# FRU_Programmer_LPC.net
KiCad netlist of a schematic drawn in Altium Designer
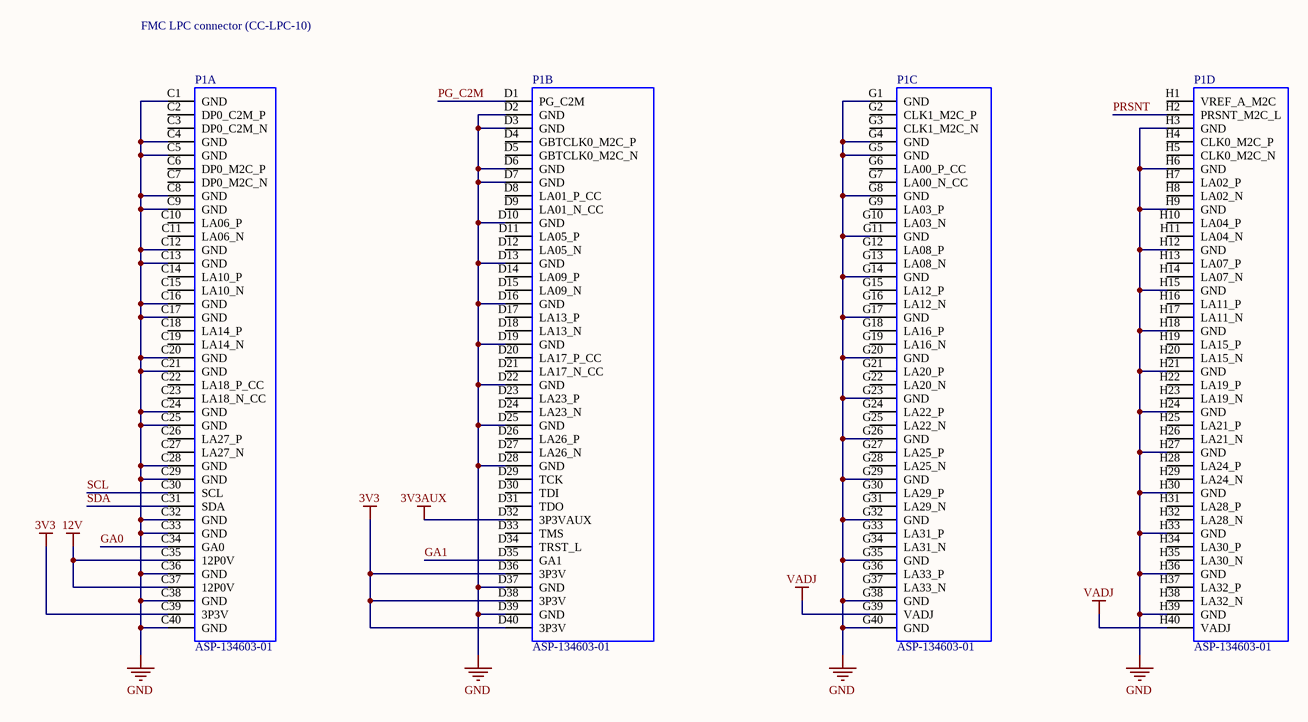
[diagram p0: FRU_Programmer_LPC.SchDoc]

(export (version "E")
  (design (tool "Eeschema 10.0.6"))
  (components
    (comp (ref "P1")
      (value "ASP-134603-01")
      (footprint "ASP-134603-01")
      (description "CC-LPC-10, FMC Low-pin count connector, lead free, 160 I/Os, female, 10 mm mated stack height")
      (fields (field (name "MANUFACTURER") "Samtec") (field (name "VITA PARTNUMBER") "CC-LPC-10"))
      (libsource (lib "VITA_57_FMC") (part "CC-LPC-10"))
    )
  )
  (nets
    (net (code "1") (name "/GA0") (class "Default")
      (node (ref "P1") (pin "C34") (pinfunction "GA0_C34") (pintype "passive"))
    )
    (net (code "2") (name "/GA1") (class "Default")
      (node (ref "P1") (pin "D35") (pinfunction "GA1_D35") (pintype "passive"))
    )
    (net (code "3") (name "/PG_C2M") (class "Default")
      (node (ref "P1") (pin "D1") (pinfunction "PG_C2M_D1") (pintype "passive"))
    )
    (net (code "4") (name "/PRSNT") (class "Default")
      (node (ref "P1") (pin "H2") (pinfunction "PRSNT_M2C_L_H2") (pintype "passive"))
    )
    (net (code "5") (name "/SCL") (class "Default")
      (node (ref "P1") (pin "C30") (pinfunction "SCL_C30") (pintype "passive"))
    )
    (net (code "6") (name "/SDA") (class "Default")
      (node (ref "P1") (pin "C31") (pinfunction "SDA_C31") (pintype "passive"))
    )
    (net (code "7") (name "3V3") (class "Default")
      (node (ref "P1") (pin "C39") (pinfunction "3P3V_C39") (pintype "passive"))
      (node (ref "P1") (pin "D36") (pinfunction "3P3V_D36") (pintype "passive"))
      (node (ref "P1") (pin "D38") (pinfunction "3P3V_D38") (pintype "passive"))
      (node (ref "P1") (pin "D40") (pinfunction "3P3V_D40") (pintype "passive"))
    )
    (net (code "8") (name "3V3AUX") (class "Default")
      (node (ref "P1") (pin "D32") (pinfunction "3P3VAUX_D32") (pintype "passive"))
    )
    (net (code "9") (name "12V") (class "Default")
      (node (ref "P1") (pin "C35") (pinfunction "12P0V_C35") (pintype "passive"))
      (node (ref "P1") (pin "C37") (pinfunction "12P0V_C37") (pintype "passive"))
    )
    (net (code "10") (name "GND") (class "Default")
      (node (ref "P1") (pin "C1") (pinfunction "GND_C1") (pintype "passive"))
      (node (ref "P1") (pin "C12") (pinfunction "GND_C12") (pintype "passive"))
      (node (ref "P1") (pin "C13") (pinfunction "GND_C13") (pintype "passive"))
      (node (ref "P1") (pin "C16") (pinfunction "GND_C16") (pintype "passive"))
      (node (ref "P1") (pin "C17") (pinfunction "GND_C17") (pintype "passive"))
      (node (ref "P1") (pin "C20") (pinfunction "GND_C20") (pintype "passive"))
      (node (ref "P1") (pin "C21") (pinfunction "GND_C21") (pintype "passive"))
      (node (ref "P1") (pin "C24") (pinfunction "GND_C24") (pintype "passive"))
      (node (ref "P1") (pin "C25") (pinfunction "GND_C25") (pintype "passive"))
      (node (ref "P1") (pin "C28") (pinfunction "GND_C28") (pintype "passive"))
      (node (ref "P1") (pin "C29") (pinfunction "GND_C29") (pintype "passive"))
      (node (ref "P1") (pin "C32") (pinfunction "GND_C32") (pintype "passive"))
      (node (ref "P1") (pin "C33") (pinfunction "GND_C33") (pintype "passive"))
      (node (ref "P1") (pin "C36") (pinfunction "GND_C36") (pintype "passive"))
      (node (ref "P1") (pin "C38") (pinfunction "GND_C38") (pintype "passive"))
      (node (ref "P1") (pin "C4") (pinfunction "GND_C4") (pintype "passive"))
      (node (ref "P1") (pin "C40") (pinfunction "GND_C40") (pintype "passive"))
      (node (ref "P1") (pin "C5") (pinfunction "GND_C5") (pintype "passive"))
      (node (ref "P1") (pin "C8") (pinfunction "GND_C8") (pintype "passive"))
      (node (ref "P1") (pin "C9") (pinfunction "GND_C9") (pintype "passive"))
      (node (ref "P1") (pin "D10") (pinfunction "GND_D10") (pintype "passive"))
      (node (ref "P1") (pin "D13") (pinfunction "GND_D13") (pintype "passive"))
      (node (ref "P1") (pin "D16") (pinfunction "GND_D16") (pintype "passive"))
      (node (ref "P1") (pin "D19") (pinfunction "GND_D19") (pintype "passive"))
      (node (ref "P1") (pin "D2") (pinfunction "GND_D2") (pintype "passive"))
      (node (ref "P1") (pin "D22") (pinfunction "GND_D22") (pintype "passive"))
      (node (ref "P1") (pin "D25") (pinfunction "GND_D25") (pintype "passive"))
      (node (ref "P1") (pin "D28") (pinfunction "GND_D28") (pintype "passive"))
      (node (ref "P1") (pin "D3") (pinfunction "GND_D3") (pintype "passive"))
      (node (ref "P1") (pin "D37") (pinfunction "GND_D37") (pintype "passive"))
      (node (ref "P1") (pin "D39") (pinfunction "GND_D39") (pintype "passive"))
      (node (ref "P1") (pin "D6") (pinfunction "GND_D6") (pintype "passive"))
      (node (ref "P1") (pin "D7") (pinfunction "GND_D7") (pintype "passive"))
      (node (ref "P1") (pin "G1") (pinfunction "GND_G1") (pintype "passive"))
      (node (ref "P1") (pin "G11") (pinfunction "GND_G11") (pintype "passive"))
      (node (ref "P1") (pin "G14") (pinfunction "GND_G14") (pintype "passive"))
      (node (ref "P1") (pin "G17") (pinfunction "GND_G17") (pintype "passive"))
      (node (ref "P1") (pin "G20") (pinfunction "GND_G20") (pintype "passive"))
      (node (ref "P1") (pin "G23") (pinfunction "GND_G23") (pintype "passive"))
      (node (ref "P1") (pin "G26") (pinfunction "GND_G26") (pintype "passive"))
      (node (ref "P1") (pin "G29") (pinfunction "GND_G29") (pintype "passive"))
      (node (ref "P1") (pin "G32") (pinfunction "GND_G32") (pintype "passive"))
      (node (ref "P1") (pin "G35") (pinfunction "GND_G35") (pintype "passive"))
      (node (ref "P1") (pin "G38") (pinfunction "GND_G38") (pintype "passive"))
      (node (ref "P1") (pin "G4") (pinfunction "GND_G4") (pintype "passive"))
      (node (ref "P1") (pin "G40") (pinfunction "GND_G40") (pintype "passive"))
      (node (ref "P1") (pin "G5") (pinfunction "GND_G5") (pintype "passive"))
      (node (ref "P1") (pin "G8") (pinfunction "GND_G8") (pintype "passive"))
      (node (ref "P1") (pin "H12") (pinfunction "GND_H12") (pintype "passive"))
      (node (ref "P1") (pin "H15") (pinfunction "GND_H15") (pintype "passive"))
      (node (ref "P1") (pin "H18") (pinfunction "GND_H18") (pintype "passive"))
      (node (ref "P1") (pin "H21") (pinfunction "GND_H21") (pintype "passive"))
      (node (ref "P1") (pin "H24") (pinfunction "GND_H24") (pintype "passive"))
      (node (ref "P1") (pin "H27") (pinfunction "GND_H27") (pintype "passive"))
      (node (ref "P1") (pin "H3") (pinfunction "GND_H3") (pintype "passive"))
      (node (ref "P1") (pin "H30") (pinfunction "GND_H30") (pintype "passive"))
      (node (ref "P1") (pin "H33") (pinfunction "GND_H33") (pintype "passive"))
      (node (ref "P1") (pin "H36") (pinfunction "GND_H36") (pintype "passive"))
      (node (ref "P1") (pin "H39") (pinfunction "GND_H39") (pintype "passive"))
      (node (ref "P1") (pin "H6") (pinfunction "GND_H6") (pintype "passive"))
      (node (ref "P1") (pin "H9") (pinfunction "GND_H9") (pintype "passive"))
    )
    (net (code "11") (name "VADJ") (class "Default")
      (node (ref "P1") (pin "G39") (pinfunction "VADJ_G39") (pintype "passive"))
      (node (ref "P1") (pin "H40") (pinfunction "VADJ_H40") (pintype "passive"))
    )
    (net (code "12") (name "unconnected-(P1A-DP0_C2M_N-PadC3)") (class "Default")
      (node (ref "P1") (pin "C3") (pinfunction "DP0_C2M_N_C3") (pintype "passive"))
    )
    (net (code "13") (name "unconnected-(P1A-DP0_C2M_P-PadC2)") (class "Default")
      (node (ref "P1") (pin "C2") (pinfunction "DP0_C2M_P_C2") (pintype "passive"))
    )
    (net (code "14") (name "unconnected-(P1A-DP0_M2C_N-PadC7)") (class "Default")
      (node (ref "P1") (pin "C7") (pinfunction "DP0_M2C_N_C7") (pintype "passive"))
    )
    (net (code "15") (name "unconnected-(P1A-DP0_M2C_P-PadC6)") (class "Default")
      (node (ref "P1") (pin "C6") (pinfunction "DP0_M2C_P_C6") (pintype "passive"))
    )
    (net (code "16") (name "unconnected-(P1A-LA06_N-PadC11)") (class "Default")
      (node (ref "P1") (pin "C11") (pinfunction "LA06_N_C11") (pintype "passive"))
    )
    (net (code "17") (name "unconnected-(P1A-LA06_P-PadC10)") (class "Default")
      (node (ref "P1") (pin "C10") (pinfunction "LA06_P_C10") (pintype "passive"))
    )
    (net (code "18") (name "unconnected-(P1A-LA10_N-PadC15)") (class "Default")
      (node (ref "P1") (pin "C15") (pinfunction "LA10_N_C15") (pintype "passive"))
    )
    (net (code "19") (name "unconnected-(P1A-LA10_P-PadC14)") (class "Default")
      (node (ref "P1") (pin "C14") (pinfunction "LA10_P_C14") (pintype "passive"))
    )
    (net (code "20") (name "unconnected-(P1A-LA14_N-PadC19)") (class "Default")
      (node (ref "P1") (pin "C19") (pinfunction "LA14_N_C19") (pintype "passive"))
    )
    (net (code "21") (name "unconnected-(P1A-LA14_P-PadC18)") (class "Default")
      (node (ref "P1") (pin "C18") (pinfunction "LA14_P_C18") (pintype "passive"))
    )
    (net (code "22") (name "unconnected-(P1A-LA18_N_CC-PadC23)") (class "Default")
      (node (ref "P1") (pin "C23") (pinfunction "LA18_N_CC_C23") (pintype "passive"))
    )
    (net (code "23") (name "unconnected-(P1A-LA18_P_CC-PadC22)") (class "Default")
      (node (ref "P1") (pin "C22") (pinfunction "LA18_P_CC_C22") (pintype "passive"))
    )
    (net (code "24") (name "unconnected-(P1A-LA27_N-PadC27)") (class "Default")
      (node (ref "P1") (pin "C27") (pinfunction "LA27_N_C27") (pintype "passive"))
    )
    (net (code "25") (name "unconnected-(P1A-LA27_P-PadC26)") (class "Default")
      (node (ref "P1") (pin "C26") (pinfunction "LA27_P_C26") (pintype "passive"))
    )
    (net (code "26") (name "unconnected-(P1B-GBTCLK0_M2C_N-PadD5)") (class "Default")
      (node (ref "P1") (pin "D5") (pinfunction "GBTCLK0_M2C_N_D5") (pintype "passive"))
    )
    (net (code "27") (name "unconnected-(P1B-GBTCLK0_M2C_P-PadD4)") (class "Default")
      (node (ref "P1") (pin "D4") (pinfunction "GBTCLK0_M2C_P_D4") (pintype "passive"))
    )
    (net (code "28") (name "unconnected-(P1B-LA01_N_CC-PadD9)") (class "Default")
      (node (ref "P1") (pin "D9") (pinfunction "LA01_N_CC_D9") (pintype "passive"))
    )
    (net (code "29") (name "unconnected-(P1B-LA01_P_CC-PadD8)") (class "Default")
      (node (ref "P1") (pin "D8") (pinfunction "LA01_P_CC_D8") (pintype "passive"))
    )
    (net (code "30") (name "unconnected-(P1B-LA05_N-PadD12)") (class "Default")
      (node (ref "P1") (pin "D12") (pinfunction "LA05_N_D12") (pintype "passive"))
    )
    (net (code "31") (name "unconnected-(P1B-LA05_P-PadD11)") (class "Default")
      (node (ref "P1") (pin "D11") (pinfunction "LA05_P_D11") (pintype "passive"))
    )
    (net (code "32") (name "unconnected-(P1B-LA09_N-PadD15)") (class "Default")
      (node (ref "P1") (pin "D15") (pinfunction "LA09_N_D15") (pintype "passive"))
    )
    (net (code "33") (name "unconnected-(P1B-LA09_P-PadD14)") (class "Default")
      (node (ref "P1") (pin "D14") (pinfunction "LA09_P_D14") (pintype "passive"))
    )
    (net (code "34") (name "unconnected-(P1B-LA13_N-PadD18)") (class "Default")
      (node (ref "P1") (pin "D18") (pinfunction "LA13_N_D18") (pintype "passive"))
    )
    (net (code "35") (name "unconnected-(P1B-LA13_P-PadD17)") (class "Default")
      (node (ref "P1") (pin "D17") (pinfunction "LA13_P_D17") (pintype "passive"))
    )
    (net (code "36") (name "unconnected-(P1B-LA17_N_CC-PadD21)") (class "Default")
      (node (ref "P1") (pin "D21") (pinfunction "LA17_N_CC_D21") (pintype "passive"))
    )
    (net (code "37") (name "unconnected-(P1B-LA17_P_CC-PadD20)") (class "Default")
      (node (ref "P1") (pin "D20") (pinfunction "LA17_P_CC_D20") (pintype "passive"))
    )
    (net (code "38") (name "unconnected-(P1B-LA23_N-PadD24)") (class "Default")
      (node (ref "P1") (pin "D24") (pinfunction "LA23_N_D24") (pintype "passive"))
    )
    (net (code "39") (name "unconnected-(P1B-LA23_P-PadD23)") (class "Default")
      (node (ref "P1") (pin "D23") (pinfunction "LA23_P_D23") (pintype "passive"))
    )
    (net (code "40") (name "unconnected-(P1B-LA26_N-PadD27)") (class "Default")
      (node (ref "P1") (pin "D27") (pinfunction "LA26_N_D27") (pintype "passive"))
    )
    (net (code "41") (name "unconnected-(P1B-LA26_P-PadD26)") (class "Default")
      (node (ref "P1") (pin "D26") (pinfunction "LA26_P_D26") (pintype "passive"))
    )
    (net (code "42") (name "unconnected-(P1B-TCK-PadD29)") (class "Default")
      (node (ref "P1") (pin "D29") (pinfunction "TCK_D29") (pintype "passive"))
    )
    (net (code "43") (name "unconnected-(P1B-TDI-PadD30)") (class "Default")
      (node (ref "P1") (pin "D30") (pinfunction "TDI_D30") (pintype "passive"))
    )
    (net (code "44") (name "unconnected-(P1B-TDO-PadD31)") (class "Default")
      (node (ref "P1") (pin "D31") (pinfunction "TDO_D31") (pintype "passive"))
    )
    (net (code "45") (name "unconnected-(P1B-TMS-PadD33)") (class "Default")
      (node (ref "P1") (pin "D33") (pinfunction "TMS_D33") (pintype "passive"))
    )
    (net (code "46") (name "unconnected-(P1B-TRST_L-PadD34)") (class "Default")
      (node (ref "P1") (pin "D34") (pinfunction "TRST_L_D34") (pintype "passive"))
    )
    (net (code "47") (name "unconnected-(P1C-CLK1_M2C_N-PadG3)") (class "Default")
      (node (ref "P1") (pin "G3") (pinfunction "CLK1_M2C_N_G3") (pintype "passive"))
    )
    (net (code "48") (name "unconnected-(P1C-CLK1_M2C_P-PadG2)") (class "Default")
      (node (ref "P1") (pin "G2") (pinfunction "CLK1_M2C_P_G2") (pintype "passive"))
    )
    (net (code "49") (name "unconnected-(P1C-LA00_N_CC-PadG7)") (class "Default")
      (node (ref "P1") (pin "G7") (pinfunction "LA00_N_CC_G7") (pintype "passive"))
    )
    (net (code "50") (name "unconnected-(P1C-LA00_P_CC-PadG6)") (class "Default")
      (node (ref "P1") (pin "G6") (pinfunction "LA00_P_CC_G6") (pintype "passive"))
    )
    (net (code "51") (name "unconnected-(P1C-LA03_N-PadG10)") (class "Default")
      (node (ref "P1") (pin "G10") (pinfunction "LA03_N_G10") (pintype "passive"))
    )
    (net (code "52") (name "unconnected-(P1C-LA03_P-PadG9)") (class "Default")
      (node (ref "P1") (pin "G9") (pinfunction "LA03_P_G9") (pintype "passive"))
    )
    (net (code "53") (name "unconnected-(P1C-LA08_N-PadG13)") (class "Default")
      (node (ref "P1") (pin "G13") (pinfunction "LA08_N_G13") (pintype "passive"))
    )
    (net (code "54") (name "unconnected-(P1C-LA08_P-PadG12)") (class "Default")
      (node (ref "P1") (pin "G12") (pinfunction "LA08_P_G12") (pintype "passive"))
    )
    (net (code "55") (name "unconnected-(P1C-LA12_N-PadG16)") (class "Default")
      (node (ref "P1") (pin "G16") (pinfunction "LA12_N_G16") (pintype "passive"))
    )
    (net (code "56") (name "unconnected-(P1C-LA12_P-PadG15)") (class "Default")
      (node (ref "P1") (pin "G15") (pinfunction "LA12_P_G15") (pintype "passive"))
    )
    (net (code "57") (name "unconnected-(P1C-LA16_N-PadG19)") (class "Default")
      (node (ref "P1") (pin "G19") (pinfunction "LA16_N_G19") (pintype "passive"))
    )
    (net (code "58") (name "unconnected-(P1C-LA16_P-PadG18)") (class "Default")
      (node (ref "P1") (pin "G18") (pinfunction "LA16_P_G18") (pintype "passive"))
    )
    (net (code "59") (name "unconnected-(P1C-LA20_N-PadG22)") (class "Default")
      (node (ref "P1") (pin "G22") (pinfunction "LA20_N_G22") (pintype "passive"))
    )
    (net (code "60") (name "unconnected-(P1C-LA20_P-PadG21)") (class "Default")
      (node (ref "P1") (pin "G21") (pinfunction "LA20_P_G21") (pintype "passive"))
    )
    (net (code "61") (name "unconnected-(P1C-LA22_N-PadG25)") (class "Default")
      (node (ref "P1") (pin "G25") (pinfunction "LA22_N_G25") (pintype "passive"))
    )
    (net (code "62") (name "unconnected-(P1C-LA22_P-PadG24)") (class "Default")
      (node (ref "P1") (pin "G24") (pinfunction "LA22_P_G24") (pintype "passive"))
    )
    (net (code "63") (name "unconnected-(P1C-LA25_N-PadG28)") (class "Default")
      (node (ref "P1") (pin "G28") (pinfunction "LA25_N_G28") (pintype "passive"))
    )
    (net (code "64") (name "unconnected-(P1C-LA25_P-PadG27)") (class "Default")
      (node (ref "P1") (pin "G27") (pinfunction "LA25_P_G27") (pintype "passive"))
    )
    (net (code "65") (name "unconnected-(P1C-LA29_N-PadG31)") (class "Default")
      (node (ref "P1") (pin "G31") (pinfunction "LA29_N_G31") (pintype "passive"))
    )
    (net (code "66") (name "unconnected-(P1C-LA29_P-PadG30)") (class "Default")
      (node (ref "P1") (pin "G30") (pinfunction "LA29_P_G30") (pintype "passive"))
    )
    (net (code "67") (name "unconnected-(P1C-LA31_N-PadG34)") (class "Default")
      (node (ref "P1") (pin "G34") (pinfunction "LA31_N_G34") (pintype "passive"))
    )
    (net (code "68") (name "unconnected-(P1C-LA31_P-PadG33)") (class "Default")
      (node (ref "P1") (pin "G33") (pinfunction "LA31_P_G33") (pintype "passive"))
    )
    (net (code "69") (name "unconnected-(P1C-LA33_N-PadG37)") (class "Default")
      (node (ref "P1") (pin "G37") (pinfunction "LA33_N_G37") (pintype "passive"))
    )
    (net (code "70") (name "unconnected-(P1C-LA33_P-PadG36)") (class "Default")
      (node (ref "P1") (pin "G36") (pinfunction "LA33_P_G36") (pintype "passive"))
    )
    (net (code "71") (name "unconnected-(P1D-CLK0_M2C_N-PadH5)") (class "Default")
      (node (ref "P1") (pin "H5") (pinfunction "CLK0_M2C_N_H5") (pintype "passive"))
    )
    (net (code "72") (name "unconnected-(P1D-CLK0_M2C_P-PadH4)") (class "Default")
      (node (ref "P1") (pin "H4") (pinfunction "CLK0_M2C_P_H4") (pintype "passive"))
    )
    (net (code "73") (name "unconnected-(P1D-LA02_N-PadH8)") (class "Default")
      (node (ref "P1") (pin "H8") (pinfunction "LA02_N_H8") (pintype "passive"))
    )
    (net (code "74") (name "unconnected-(P1D-LA02_P-PadH7)") (class "Default")
      (node (ref "P1") (pin "H7") (pinfunction "LA02_P_H7") (pintype "passive"))
    )
    (net (code "75") (name "unconnected-(P1D-LA04_N-PadH11)") (class "Default")
      (node (ref "P1") (pin "H11") (pinfunction "LA04_N_H11") (pintype "passive"))
    )
    (net (code "76") (name "unconnected-(P1D-LA04_P-PadH10)") (class "Default")
      (node (ref "P1") (pin "H10") (pinfunction "LA04_P_H10") (pintype "passive"))
    )
    (net (code "77") (name "unconnected-(P1D-LA07_N-PadH14)") (class "Default")
      (node (ref "P1") (pin "H14") (pinfunction "LA07_N_H14") (pintype "passive"))
    )
    (net (code "78") (name "unconnected-(P1D-LA07_P-PadH13)") (class "Default")
      (node (ref "P1") (pin "H13") (pinfunction "LA07_P_H13") (pintype "passive"))
    )
    (net (code "79") (name "unconnected-(P1D-LA11_N-PadH17)") (class "Default")
      (node (ref "P1") (pin "H17") (pinfunction "LA11_N_H17") (pintype "passive"))
    )
    (net (code "80") (name "unconnected-(P1D-LA11_P-PadH16)") (class "Default")
      (node (ref "P1") (pin "H16") (pinfunction "LA11_P_H16") (pintype "passive"))
    )
    (net (code "81") (name "unconnected-(P1D-LA15_N-PadH20)") (class "Default")
      (node (ref "P1") (pin "H20") (pinfunction "LA15_N_H20") (pintype "passive"))
    )
    (net (code "82") (name "unconnected-(P1D-LA15_P-PadH19)") (class "Default")
      (node (ref "P1") (pin "H19") (pinfunction "LA15_P_H19") (pintype "passive"))
    )
    (net (code "83") (name "unconnected-(P1D-LA19_N-PadH23)") (class "Default")
      (node (ref "P1") (pin "H23") (pinfunction "LA19_N_H23") (pintype "passive"))
    )
    (net (code "84") (name "unconnected-(P1D-LA19_P-PadH22)") (class "Default")
      (node (ref "P1") (pin "H22") (pinfunction "LA19_P_H22") (pintype "passive"))
    )
    (net (code "85") (name "unconnected-(P1D-LA21_N-PadH26)") (class "Default")
      (node (ref "P1") (pin "H26") (pinfunction "LA21_N_H26") (pintype "passive"))
    )
    (net (code "86") (name "unconnected-(P1D-LA21_P-PadH25)") (class "Default")
      (node (ref "P1") (pin "H25") (pinfunction "LA21_P_H25") (pintype "passive"))
    )
    (net (code "87") (name "unconnected-(P1D-LA24_N-PadH29)") (class "Default")
      (node (ref "P1") (pin "H29") (pinfunction "LA24_N_H29") (pintype "passive"))
    )
    (net (code "88") (name "unconnected-(P1D-LA24_P-PadH28)") (class "Default")
      (node (ref "P1") (pin "H28") (pinfunction "LA24_P_H28") (pintype "passive"))
    )
    (net (code "89") (name "unconnected-(P1D-LA28_N-PadH32)") (class "Default")
      (node (ref "P1") (pin "H32") (pinfunction "LA28_N_H32") (pintype "passive"))
    )
    (net (code "90") (name "unconnected-(P1D-LA28_P-PadH31)") (class "Default")
      (node (ref "P1") (pin "H31") (pinfunction "LA28_P_H31") (pintype "passive"))
    )
    (net (code "91") (name "unconnected-(P1D-LA30_N-PadH35)") (class "Default")
      (node (ref "P1") (pin "H35") (pinfunction "LA30_N_H35") (pintype "passive"))
    )
    (net (code "92") (name "unconnected-(P1D-LA30_P-PadH34)") (class "Default")
      (node (ref "P1") (pin "H34") (pinfunction "LA30_P_H34") (pintype "passive"))
    )
    (net (code "93") (name "unconnected-(P1D-LA32_N-PadH38)") (class "Default")
      (node (ref "P1") (pin "H38") (pinfunction "LA32_N_H38") (pintype "passive"))
    )
    (net (code "94") (name "unconnected-(P1D-LA32_P-PadH37)") (class "Default")
      (node (ref "P1") (pin "H37") (pinfunction "LA32_P_H37") (pintype "passive"))
    )
    (net (code "95") (name "unconnected-(P1D-VREF_A_M2C-PadH1)") (class "Default")
      (node (ref "P1") (pin "H1") (pinfunction "VREF_A_M2C_H1") (pintype "passive"))
    )
  )
)
